# Sheet_1_2025-12-19.net
KiCad netlist of a schematic drawn in Altium Designer
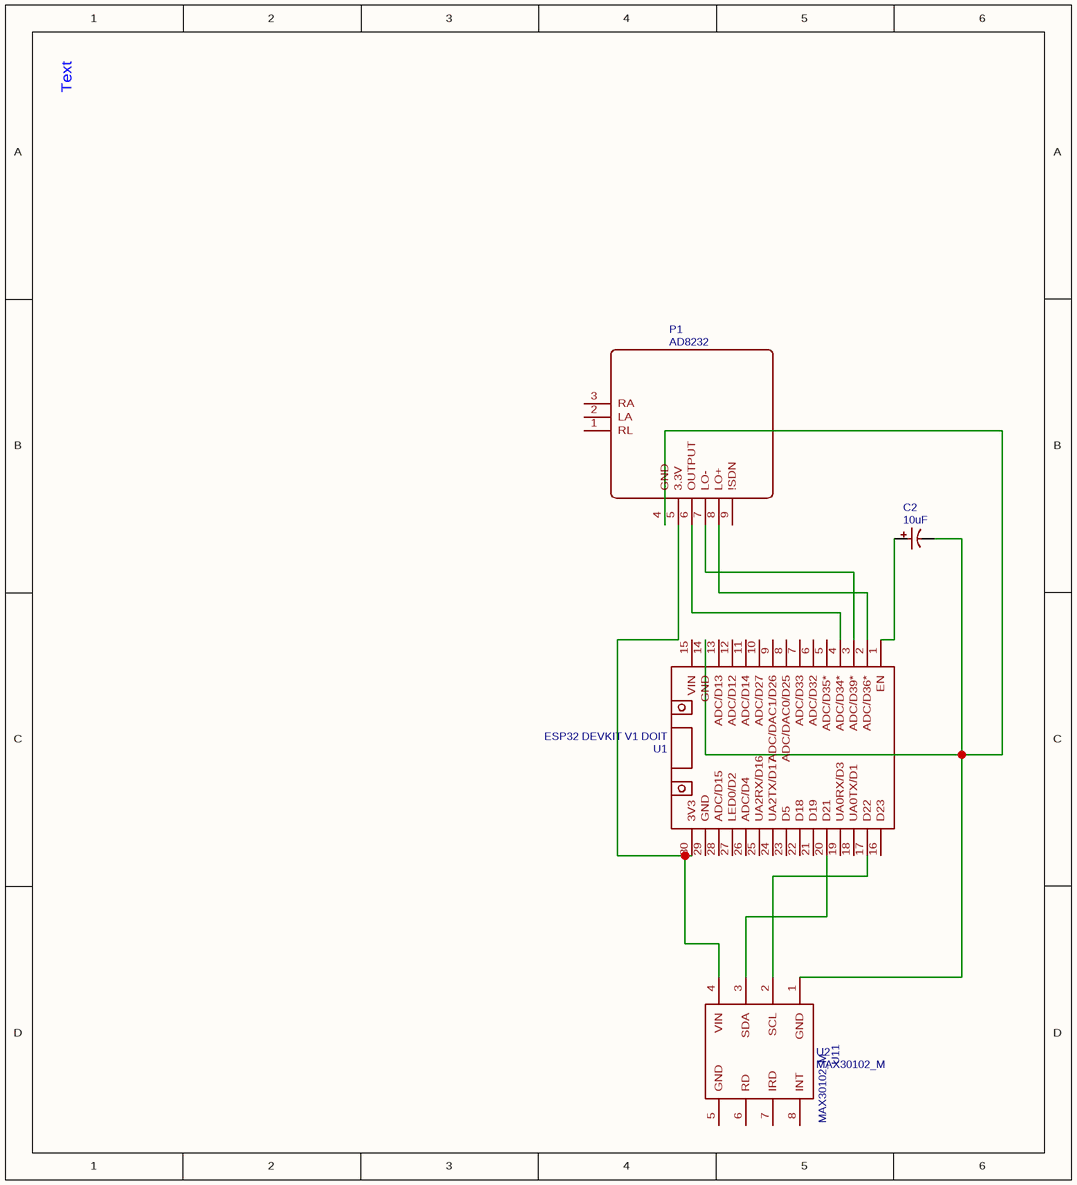
[diagram p0: Sheet_1_2025-12-19.schdoc]

(export (version "E")
  (design (tool "Eeschema 10.0.6"))
  (components
    (comp (ref "C2")
      (value "10uF")
      (fields
        (field (name "MANUFACTURER") "CX(承兴)")
        (field (name "MANUFACTURER PART") "KM476M016D11RR0VH2FP0")
        (field (name "CONTRIBUTOR") "Hacket")
      )
      (libsource (lib "altium-import") (part "root_0_10uF_"))
    )
    (comp (ref "P1") (value "AD8232") (libsource (lib "altium-import") (part "root_0_AD8232_")))
    (comp (ref "U1")
      (value "ESP32 DEVKIT V1 DOIT")
      (fields (field (name "CONTRIBUTOR") "Furkan İLBEYİ"))
      (libsource (lib "altium-import") (part "root_1_ESP32 DEVKIT V1 DOIT_"))
    )
    (comp (ref "U2")
      (value "MAX30102_M")
      (fields (field (name "CONTRIBUTOR") "xconicsembedded"))
      (libsource (lib "altium-import") (part "root_3_MAX30102_M_"))
    )
  )
  (nets
    (net (code "1") (name "Net-(P1-3.3V)") (class "Default")
      (node (ref "P1") (pin "5") (pinfunction "3.3V_5") (pintype "passive"))
      (node (ref "U1") (pin "30") (pinfunction "3V3_30") (pintype "passive"))
      (node (ref "U2") (pin "4") (pinfunction "VIN_4") (pintype "passive"))
    )
    (net (code "2") (name "Net-(P1-GND)") (class "Default")
      (node (ref "C2") (pin "2") (pinfunction "2_2") (pintype "passive"))
      (node (ref "P1") (pin "4") (pinfunction "GND_4") (pintype "passive"))
      (node (ref "U1") (pin "14") (pinfunction "GND_14") (pintype "passive"))
      (node (ref "U2") (pin "1") (pinfunction "GND_1") (pintype "passive"))
    )
    (net (code "3") (name "Net-(P1-LO+)") (class "Default")
      (node (ref "P1") (pin "8") (pinfunction "LO+_8") (pintype "passive"))
      (node (ref "U1") (pin "2") (pinfunction "ADC/D36*_2") (pintype "passive"))
    )
    (net (code "4") (name "Net-(P1-LO-)") (class "Default")
      (node (ref "P1") (pin "7") (pinfunction "LO-_7") (pintype "passive"))
      (node (ref "U1") (pin "3") (pinfunction "ADC/D39*_3") (pintype "passive"))
    )
    (net (code "5") (name "Net-(P1-OUTPUT)") (class "Default")
      (node (ref "P1") (pin "6") (pinfunction "OUTPUT_6") (pintype "passive"))
      (node (ref "U1") (pin "4") (pinfunction "ADC/D34*_4") (pintype "passive"))
    )
    (net (code "6") (name "Net-(U1-D21)") (class "Default")
      (node (ref "U1") (pin "20") (pinfunction "D21_20") (pintype "passive"))
      (node (ref "U2") (pin "3") (pinfunction "SDA_3") (pintype "passive"))
    )
    (net (code "7") (name "Net-(U1-D22)") (class "Default")
      (node (ref "U1") (pin "17") (pinfunction "D22_17") (pintype "passive"))
      (node (ref "U2") (pin "2") (pinfunction "SCL_2") (pintype "passive"))
    )
    (net (code "8") (name "Net-(U1-EN)") (class "Default")
      (node (ref "C2") (pin "1") (pinfunction "1_1") (pintype "passive"))
      (node (ref "U1") (pin "1") (pinfunction "EN_1") (pintype "passive"))
    )
    (net (code "9") (name "unconnected-(P1-!SDN-Pad9)") (class "Default")
      (node (ref "P1") (pin "9") (pinfunction "!SDN_9") (pintype "passive"))
    )
    (net (code "10") (name "unconnected-(P1-LA-Pad2)") (class "Default")
      (node (ref "P1") (pin "2") (pinfunction "LA_2") (pintype "passive"))
    )
    (net (code "11") (name "unconnected-(P1-RA-Pad3)") (class "Default")
      (node (ref "P1") (pin "3") (pinfunction "RA_3") (pintype "passive"))
    )
    (net (code "12") (name "unconnected-(P1-RL-Pad1)") (class "Default")
      (node (ref "P1") (pin "1") (pinfunction "RL_1") (pintype "passive"))
    )
    (net (code "13") (name "unconnected-(U1-ADC{slash}D4-Pad26)") (class "Default")
      (node (ref "U1") (pin "26") (pinfunction "ADC/D4_26") (pintype "passive"))
    )
    (net (code "14") (name "unconnected-(U1-ADC{slash}D12-Pad12)") (class "Default")
      (node (ref "U1") (pin "12") (pinfunction "ADC/D12_12") (pintype "passive"))
    )
    (net (code "15") (name "unconnected-(U1-ADC{slash}D13-Pad13)") (class "Default")
      (node (ref "U1") (pin "13") (pinfunction "ADC/D13_13") (pintype "passive"))
    )
    (net (code "16") (name "unconnected-(U1-ADC{slash}D14-Pad11)") (class "Default")
      (node (ref "U1") (pin "11") (pinfunction "ADC/D14_11") (pintype "passive"))
    )
    (net (code "17") (name "unconnected-(U1-ADC{slash}D15-Pad28)") (class "Default")
      (node (ref "U1") (pin "28") (pinfunction "ADC/D15_28") (pintype "passive"))
    )
    (net (code "18") (name "unconnected-(U1-ADC{slash}D27-Pad10)") (class "Default")
      (node (ref "U1") (pin "10") (pinfunction "ADC/D27_10") (pintype "passive"))
    )
    (net (code "19") (name "unconnected-(U1-ADC{slash}D32-Pad6)") (class "Default")
      (node (ref "U1") (pin "6") (pinfunction "ADC/D32_6") (pintype "passive"))
    )
    (net (code "20") (name "unconnected-(U1-ADC{slash}D33-Pad7)") (class "Default")
      (node (ref "U1") (pin "7") (pinfunction "ADC/D33_7") (pintype "passive"))
    )
    (net (code "21") (name "unconnected-(U1-ADC{slash}D35*-Pad5)") (class "Default")
      (node (ref "U1") (pin "5") (pinfunction "ADC/D35*_5") (pintype "passive"))
    )
    (net (code "22") (name "unconnected-(U1-ADC{slash}DAC0{slash}D25-Pad8)") (class "Default")
      (node (ref "U1") (pin "8") (pinfunction "ADC/DAC0/D25_8") (pintype "passive"))
    )
    (net (code "23") (name "unconnected-(U1-ADC{slash}DAC1{slash}D26-Pad9)") (class "Default")
      (node (ref "U1") (pin "9") (pinfunction "ADC/DAC1/D26_9") (pintype "passive"))
    )
    (net (code "24") (name "unconnected-(U1-D5-Pad23)") (class "Default")
      (node (ref "U1") (pin "23") (pinfunction "D5_23") (pintype "passive"))
    )
    (net (code "25") (name "unconnected-(U1-D18-Pad22)") (class "Default")
      (node (ref "U1") (pin "22") (pinfunction "D18_22") (pintype "passive"))
    )
    (net (code "26") (name "unconnected-(U1-D19-Pad21)") (class "Default")
      (node (ref "U1") (pin "21") (pinfunction "D19_21") (pintype "passive"))
    )
    (net (code "27") (name "unconnected-(U1-D23-Pad16)") (class "Default")
      (node (ref "U1") (pin "16") (pinfunction "D23_16") (pintype "passive"))
    )
    (net (code "28") (name "unconnected-(U1-GND-Pad29)") (class "Default")
      (node (ref "U1") (pin "29") (pinfunction "GND_29") (pintype "passive"))
    )
    (net (code "29") (name "unconnected-(U1-LED0{slash}D2-Pad27)") (class "Default")
      (node (ref "U1") (pin "27") (pinfunction "LED0/D2_27") (pintype "passive"))
    )
    (net (code "30") (name "unconnected-(U1-UA0RX{slash}D3-Pad19)") (class "Default")
      (node (ref "U1") (pin "19") (pinfunction "UA0RX/D3_19") (pintype "passive"))
    )
    (net (code "31") (name "unconnected-(U1-UA0TX{slash}D1-Pad18)") (class "Default")
      (node (ref "U1") (pin "18") (pinfunction "UA0TX/D1_18") (pintype "passive"))
    )
    (net (code "32") (name "unconnected-(U1-UA2RX{slash}D16-Pad25)") (class "Default")
      (node (ref "U1") (pin "25") (pinfunction "UA2RX/D16_25") (pintype "passive"))
    )
    (net (code "33") (name "unconnected-(U1-UA2TX{slash}D17-Pad24)") (class "Default")
      (node (ref "U1") (pin "24") (pinfunction "UA2TX/D17_24") (pintype "passive"))
    )
    (net (code "34") (name "unconnected-(U1-VIN-Pad15)") (class "Default")
      (node (ref "U1") (pin "15") (pinfunction "VIN_15") (pintype "passive"))
    )
    (net (code "35") (name "unconnected-(U2-GND-Pad5)") (class "Default")
      (node (ref "U2") (pin "5") (pinfunction "GND_5") (pintype "passive"))
    )
    (net (code "36") (name "unconnected-(U2-INT-Pad8)") (class "Default")
      (node (ref "U2") (pin "8") (pinfunction "INT_8") (pintype "passive"))
    )
    (net (code "37") (name "unconnected-(U2-IRD-Pad7)") (class "Default")
      (node (ref "U2") (pin "7") (pinfunction "IRD_7") (pintype "passive"))
    )
    (net (code "38") (name "unconnected-(U2-RD-Pad6)") (class "Default")
      (node (ref "U2") (pin "6") (pinfunction "RD_6") (pintype "passive"))
    )
  )
)
